# RN4020_BLE_V1.net
KiCad netlist of a schematic drawn in EAGLE
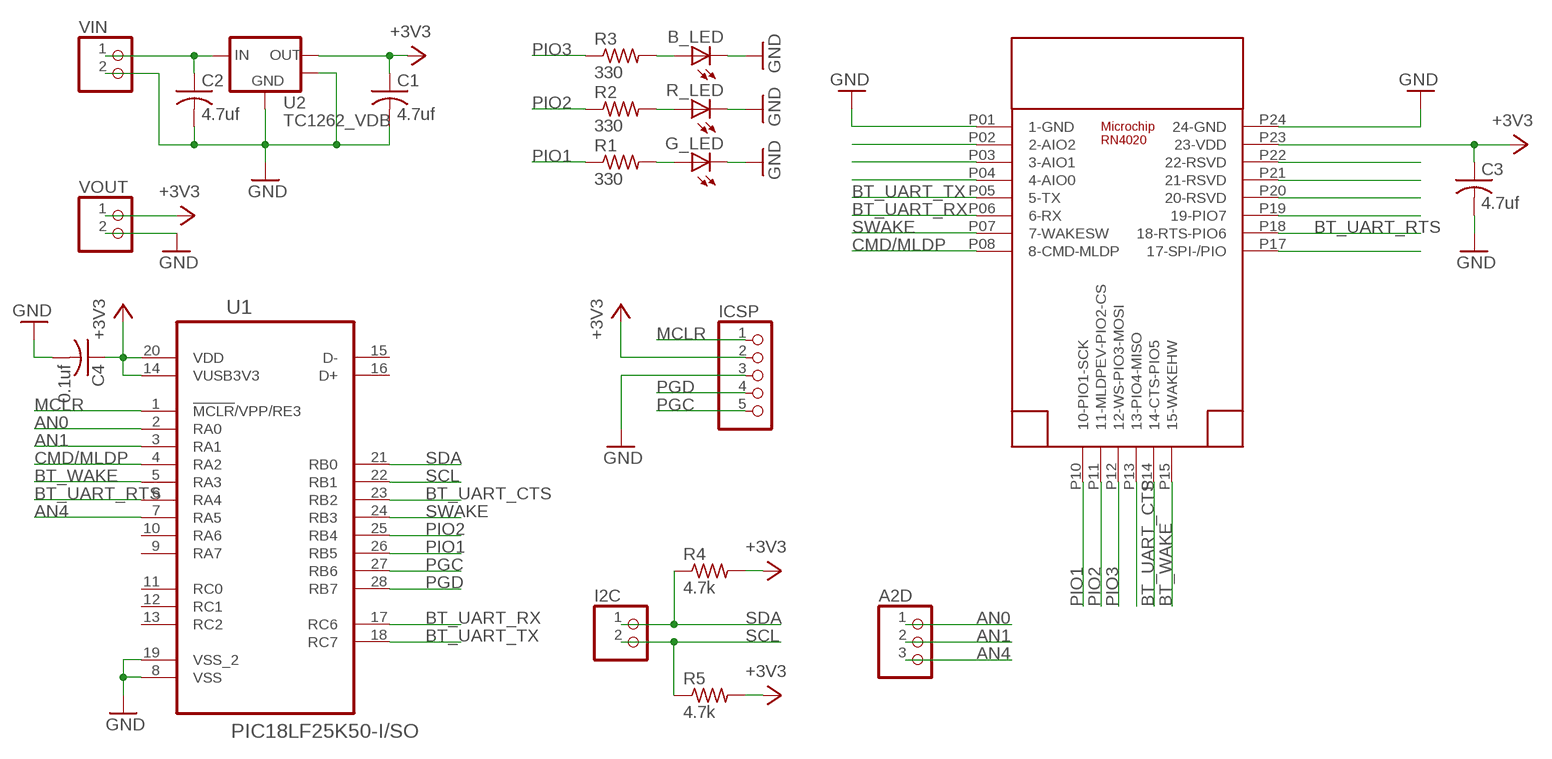
[diagram p0: schematic, sheet 1]

(export (version "E")
  (design (tool "Eeschema 10.0.6"))
  (components
    (comp (ref "A2D")
      (value "PINHD-1X3")
      (footprint "eagle-import:1X03")
      (libsource (lib "eagle-import") (part "PINHD-1X3"))
    )
    (comp (ref "B_LED")
      (value "LEDSMT1206")
      (footprint "eagle-import:1206")
      (libsource (lib "eagle-import") (part "LEDSMT1206"))
    )
    (comp (ref "C1")
      (value "4.7uf")
      (footprint "eagle-import:C1206")
      (libsource (lib "eagle-import") (part "C-USC1206"))
    )
    (comp (ref "C2")
      (value "4.7uf")
      (footprint "eagle-import:C1206")
      (libsource (lib "eagle-import") (part "C-USC1206"))
    )
    (comp (ref "C3")
      (value "4.7uf")
      (footprint "eagle-import:C1206")
      (libsource (lib "eagle-import") (part "C-USC1206"))
    )
    (comp (ref "C4")
      (value "0.1uf")
      (footprint "eagle-import:C1206")
      (libsource (lib "eagle-import") (part "C-USC1206"))
    )
    (comp (ref "G_LED")
      (value "LEDSMT1206")
      (footprint "eagle-import:1206")
      (libsource (lib "eagle-import") (part "LEDSMT1206"))
    )
    (comp (ref "I2C")
      (value "PINHD-1X2")
      (footprint "eagle-import:1X02")
      (libsource (lib "eagle-import") (part "PINHD-1X2"))
    )
    (comp (ref "ICSP")
      (value "PINHD-1X5")
      (footprint "eagle-import:1X05")
      (libsource (lib "eagle-import") (part "PINHD-1X5"))
    )
    (comp (ref "R1")
      (value "330")
      (footprint "eagle-import:R1206")
      (libsource (lib "eagle-import") (part "R-US_R1206"))
    )
    (comp (ref "R2")
      (value "330")
      (footprint "eagle-import:R1206")
      (libsource (lib "eagle-import") (part "R-US_R1206"))
    )
    (comp (ref "R3")
      (value "330")
      (footprint "eagle-import:R1206")
      (libsource (lib "eagle-import") (part "R-US_R1206"))
    )
    (comp (ref "R4")
      (value "4.7k")
      (footprint "eagle-import:R1206")
      (libsource (lib "eagle-import") (part "R-US_R1206"))
    )
    (comp (ref "R5")
      (value "4.7k")
      (footprint "eagle-import:R1206")
      (libsource (lib "eagle-import") (part "R-US_R1206"))
    )
    (comp (ref "R_LED")
      (value "LEDSMT1206")
      (footprint "eagle-import:1206")
      (libsource (lib "eagle-import") (part "LEDSMT1206"))
    )
    (comp (ref "U$1")
      (value "RN4020")
      (footprint "eagle-import:RN4020SMD")
      (libsource (lib "eagle-import") (part "RN4020"))
    )
    (comp (ref "U1")
      (value "PIC18LF25K50-I/SO")
      (footprint "eagle-import:SOIC127P1032X265-28N")
      (libsource (lib "eagle-import") (part "PIC18LF25K50-I/SO"))
    )
    (comp (ref "U2")
      (value "TC1262_VDB")
      (footprint "eagle-import:SOT-223-3")
      (libsource (lib "eagle-import") (part "TC1262_VDB"))
    )
    (comp (ref "VIN")
      (value "PINHD-1X2")
      (footprint "eagle-import:1X02")
      (libsource (lib "eagle-import") (part "PINHD-1X2"))
    )
    (comp (ref "VOUT")
      (value "PINHD-1X2")
      (footprint "eagle-import:1X02")
      (libsource (lib "eagle-import") (part "PINHD-1X2"))
    )
  )
  (nets
    (net (code "1") (name "+3V3") (class "Default")
      (node (ref "C1") (pin "1") (pinfunction "1_1") (pintype "passive"))
      (node (ref "C3") (pin "1") (pinfunction "1_1") (pintype "passive"))
      (node (ref "C4") (pin "1") (pinfunction "1_1") (pintype "passive"))
      (node (ref "ICSP") (pin "2") (pinfunction "2_2") (pintype "passive"))
      (node (ref "R4") (pin "2") (pinfunction "2_2") (pintype "passive"))
      (node (ref "R5") (pin "2") (pinfunction "2_2") (pintype "passive"))
      (node (ref "U$1") (pin "P23") (pinfunction "23-VDD_P23") (pintype "bidirectional"))
      (node (ref "U1") (pin "14") (pinfunction "VUSB3V3_14") (pintype "power_in"))
      (node (ref "U1") (pin "20") (pinfunction "VDD_20") (pintype "power_in"))
      (node (ref "U2") (pin "3") (pinfunction "VOUT_3") (pintype "bidirectional"))
      (node (ref "VOUT") (pin "1") (pinfunction "1_1") (pintype "passive"))
    )
    (net (code "2") (name "/AN0") (class "Default")
      (node (ref "A2D") (pin "1") (pinfunction "1_1") (pintype "passive"))
      (node (ref "U1") (pin "2") (pinfunction "RA0_2") (pintype "bidirectional"))
    )
    (net (code "3") (name "/AN1") (class "Default")
      (node (ref "A2D") (pin "2") (pinfunction "2_2") (pintype "passive"))
      (node (ref "U1") (pin "3") (pinfunction "RA1_3") (pintype "bidirectional"))
    )
    (net (code "4") (name "/AN4") (class "Default")
      (node (ref "A2D") (pin "3") (pinfunction "3_3") (pintype "passive"))
      (node (ref "U1") (pin "7") (pinfunction "RA5_7") (pintype "bidirectional"))
    )
    (net (code "5") (name "/BT_UART_CTS") (class "Default")
      (node (ref "U$1") (pin "P14") (pinfunction "14-CTS-PIO5_P14") (pintype "bidirectional"))
      (node (ref "U1") (pin "23") (pinfunction "RB2_23") (pintype "bidirectional"))
    )
    (net (code "6") (name "/BT_UART_RTS") (class "Default")
      (node (ref "U$1") (pin "P18") (pinfunction "18-RTS-PIO6_P18") (pintype "bidirectional"))
      (node (ref "U1") (pin "6") (pinfunction "RA4_6") (pintype "bidirectional"))
    )
    (net (code "7") (name "/BT_UART_RX") (class "Default")
      (node (ref "U$1") (pin "P06") (pinfunction "6-RX_P06") (pintype "bidirectional"))
      (node (ref "U1") (pin "17") (pinfunction "RC6_17") (pintype "bidirectional"))
    )
    (net (code "8") (name "/BT_UART_TX") (class "Default")
      (node (ref "U$1") (pin "P05") (pinfunction "5-TX_P05") (pintype "bidirectional"))
      (node (ref "U1") (pin "18") (pinfunction "RC7_18") (pintype "bidirectional"))
    )
    (net (code "9") (name "/BT_WAKE") (class "Default")
      (node (ref "U$1") (pin "P15") (pinfunction "15-WAKEHW_P15") (pintype "bidirectional"))
      (node (ref "U1") (pin "5") (pinfunction "RA3_5") (pintype "bidirectional"))
    )
    (net (code "10") (name "/CMD{slash}MLDP") (class "Default")
      (node (ref "U$1") (pin "P08") (pinfunction "8-CMD-MLDP_P08") (pintype "bidirectional"))
      (node (ref "U1") (pin "4") (pinfunction "RA2_4") (pintype "bidirectional"))
    )
    (net (code "11") (name "/MCLR") (class "Default")
      (node (ref "ICSP") (pin "1") (pinfunction "1_1") (pintype "passive"))
      (node (ref "U1") (pin "1") (pinfunction "~{MCLR}/VPP/RE3_1") (pintype "bidirectional"))
    )
    (net (code "12") (name "/PGC") (class "Default")
      (node (ref "ICSP") (pin "5") (pinfunction "5_5") (pintype "passive"))
      (node (ref "U1") (pin "27") (pinfunction "RB6_27") (pintype "bidirectional"))
    )
    (net (code "13") (name "/PGD") (class "Default")
      (node (ref "ICSP") (pin "4") (pinfunction "4_4") (pintype "passive"))
      (node (ref "U1") (pin "28") (pinfunction "RB7_28") (pintype "bidirectional"))
    )
    (net (code "14") (name "/PIO1") (class "Default")
      (node (ref "R1") (pin "1") (pinfunction "1_1") (pintype "passive"))
      (node (ref "U$1") (pin "P10") (pinfunction "10-PIO1-SCK_P10") (pintype "bidirectional"))
      (node (ref "U1") (pin "26") (pinfunction "RB5_26") (pintype "bidirectional"))
    )
    (net (code "15") (name "/PIO2") (class "Default")
      (node (ref "R2") (pin "1") (pinfunction "1_1") (pintype "passive"))
      (node (ref "U$1") (pin "P11") (pinfunction "11-MLDPEV-PIO2-CS_P11") (pintype "bidirectional"))
      (node (ref "U1") (pin "25") (pinfunction "RB4_25") (pintype "bidirectional"))
    )
    (net (code "16") (name "/PIO3") (class "Default")
      (node (ref "R3") (pin "1") (pinfunction "1_1") (pintype "passive"))
      (node (ref "U$1") (pin "P12") (pinfunction "12-WS-PIO3-MOSI_P12") (pintype "bidirectional"))
    )
    (net (code "17") (name "/SCL") (class "Default")
      (node (ref "I2C") (pin "2") (pinfunction "2_2") (pintype "passive"))
      (node (ref "R5") (pin "1") (pinfunction "1_1") (pintype "passive"))
      (node (ref "U1") (pin "22") (pinfunction "RB1_22") (pintype "bidirectional"))
    )
    (net (code "18") (name "/SDA") (class "Default")
      (node (ref "I2C") (pin "1") (pinfunction "1_1") (pintype "passive"))
      (node (ref "R4") (pin "1") (pinfunction "1_1") (pintype "passive"))
      (node (ref "U1") (pin "21") (pinfunction "RB0_21") (pintype "bidirectional"))
    )
    (net (code "19") (name "/SWAKE") (class "Default")
      (node (ref "U$1") (pin "P07") (pinfunction "7-WAKESW_P07") (pintype "bidirectional"))
      (node (ref "U1") (pin "24") (pinfunction "RB3_24") (pintype "bidirectional"))
    )
    (net (code "20") (name "GND") (class "Default")
      (node (ref "B_LED") (pin "C") (pinfunction "C_C") (pintype "passive"))
      (node (ref "C1") (pin "2") (pinfunction "2_2") (pintype "passive"))
      (node (ref "C2") (pin "2") (pinfunction "2_2") (pintype "passive"))
      (node (ref "C3") (pin "2") (pinfunction "2_2") (pintype "passive"))
      (node (ref "C4") (pin "2") (pinfunction "2_2") (pintype "passive"))
      (node (ref "G_LED") (pin "C") (pinfunction "C_C") (pintype "passive"))
      (node (ref "ICSP") (pin "3") (pinfunction "3_3") (pintype "passive"))
      (node (ref "R_LED") (pin "C") (pinfunction "C_C") (pintype "passive"))
      (node (ref "U$1") (pin "P01") (pinfunction "1-GND_P01") (pintype "bidirectional"))
      (node (ref "U$1") (pin "P24") (pinfunction "24-GND_P24") (pintype "bidirectional"))
      (node (ref "U1") (pin "19") (pinfunction "VSS_2_19") (pintype "power_in"))
      (node (ref "U1") (pin "8") (pinfunction "VSS_8") (pintype "power_in"))
      (node (ref "U2") (pin "2") (pinfunction "GND_2") (pintype "bidirectional"))
      (node (ref "U2") (pin "4") (pinfunction "TAB_4") (pintype "bidirectional"))
      (node (ref "VIN") (pin "2") (pinfunction "2_2") (pintype "passive"))
      (node (ref "VOUT") (pin "2") (pinfunction "2_2") (pintype "passive"))
    )
    (net (code "21") (name "Net-(B_LED-PadA)") (class "Default")
      (node (ref "B_LED") (pin "A") (pinfunction "A_A") (pintype "passive"))
      (node (ref "R3") (pin "2") (pinfunction "2_2") (pintype "passive"))
    )
    (net (code "22") (name "Net-(G_LED-PadA)") (class "Default")
      (node (ref "G_LED") (pin "A") (pinfunction "A_A") (pintype "passive"))
      (node (ref "R1") (pin "2") (pinfunction "2_2") (pintype "passive"))
    )
    (net (code "23") (name "Net-(R2-Pad2)") (class "Default")
      (node (ref "R2") (pin "2") (pinfunction "2_2") (pintype "passive"))
      (node (ref "R_LED") (pin "A") (pinfunction "A_A") (pintype "passive"))
    )
    (net (code "24") (name "Net-(U2-VIN)") (class "Default")
      (node (ref "C2") (pin "1") (pinfunction "1_1") (pintype "passive"))
      (node (ref "U2") (pin "1") (pinfunction "VIN_1") (pintype "bidirectional"))
      (node (ref "VIN") (pin "1") (pinfunction "1_1") (pintype "passive"))
    )
    (net (code "25") (name "unconnected-(U$1-2-AIO2-PadP02)") (class "Default")
      (node (ref "U$1") (pin "P02") (pinfunction "2-AIO2_P02") (pintype "bidirectional"))
    )
    (net (code "26") (name "unconnected-(U$1-3-AIO1-PadP03)") (class "Default")
      (node (ref "U$1") (pin "P03") (pinfunction "3-AIO1_P03") (pintype "bidirectional"))
    )
    (net (code "27") (name "unconnected-(U$1-4-AIO0-PadP04)") (class "Default")
      (node (ref "U$1") (pin "P04") (pinfunction "4-AIO0_P04") (pintype "bidirectional"))
    )
    (net (code "28") (name "unconnected-(U$1-13-PIO4-MISO-PadP13)") (class "Default")
      (node (ref "U$1") (pin "P13") (pinfunction "13-PIO4-MISO_P13") (pintype "bidirectional"))
    )
    (net (code "29") (name "unconnected-(U$1-17-SPI-{slash}PIO-PadP17)") (class "Default")
      (node (ref "U$1") (pin "P17") (pinfunction "17-SPI-/PIO_P17") (pintype "bidirectional"))
    )
    (net (code "30") (name "unconnected-(U$1-19-PIO7-PadP19)") (class "Default")
      (node (ref "U$1") (pin "P19") (pinfunction "19-PIO7_P19") (pintype "bidirectional"))
    )
    (net (code "31") (name "unconnected-(U$1-20-RSVD-PadP20)") (class "Default")
      (node (ref "U$1") (pin "P20") (pinfunction "20-RSVD_P20") (pintype "bidirectional"))
    )
    (net (code "32") (name "unconnected-(U$1-21-RSVD-PadP21)") (class "Default")
      (node (ref "U$1") (pin "P21") (pinfunction "21-RSVD_P21") (pintype "bidirectional"))
    )
    (net (code "33") (name "unconnected-(U$1-22-RSVD-PadP22)") (class "Default")
      (node (ref "U$1") (pin "P22") (pinfunction "22-RSVD_P22") (pintype "bidirectional"))
    )
    (net (code "34") (name "unconnected-(U1-D+-Pad16)") (class "Default")
      (node (ref "U1") (pin "16") (pinfunction "D+_16") (pintype "passive"))
    )
    (net (code "35") (name "unconnected-(U1-D--Pad15)") (class "Default")
      (node (ref "U1") (pin "15") (pinfunction "D-_15") (pintype "passive"))
    )
    (net (code "36") (name "unconnected-(U1-RA6-Pad10)") (class "Default")
      (node (ref "U1") (pin "10") (pinfunction "RA6_10") (pintype "bidirectional"))
    )
    (net (code "37") (name "unconnected-(U1-RA7-Pad9)") (class "Default")
      (node (ref "U1") (pin "9") (pinfunction "RA7_9") (pintype "bidirectional"))
    )
    (net (code "38") (name "unconnected-(U1-RC0-Pad11)") (class "Default")
      (node (ref "U1") (pin "11") (pinfunction "RC0_11") (pintype "bidirectional"))
    )
    (net (code "39") (name "unconnected-(U1-RC1-Pad12)") (class "Default")
      (node (ref "U1") (pin "12") (pinfunction "RC1_12") (pintype "bidirectional"))
    )
    (net (code "40") (name "unconnected-(U1-RC2-Pad13)") (class "Default")
      (node (ref "U1") (pin "13") (pinfunction "RC2_13") (pintype "bidirectional"))
    )
  )
)
